# MRCS-Nano-Ard-Relay-Breakout.net
KiCad netlist of a schematic drawn in EAGLE
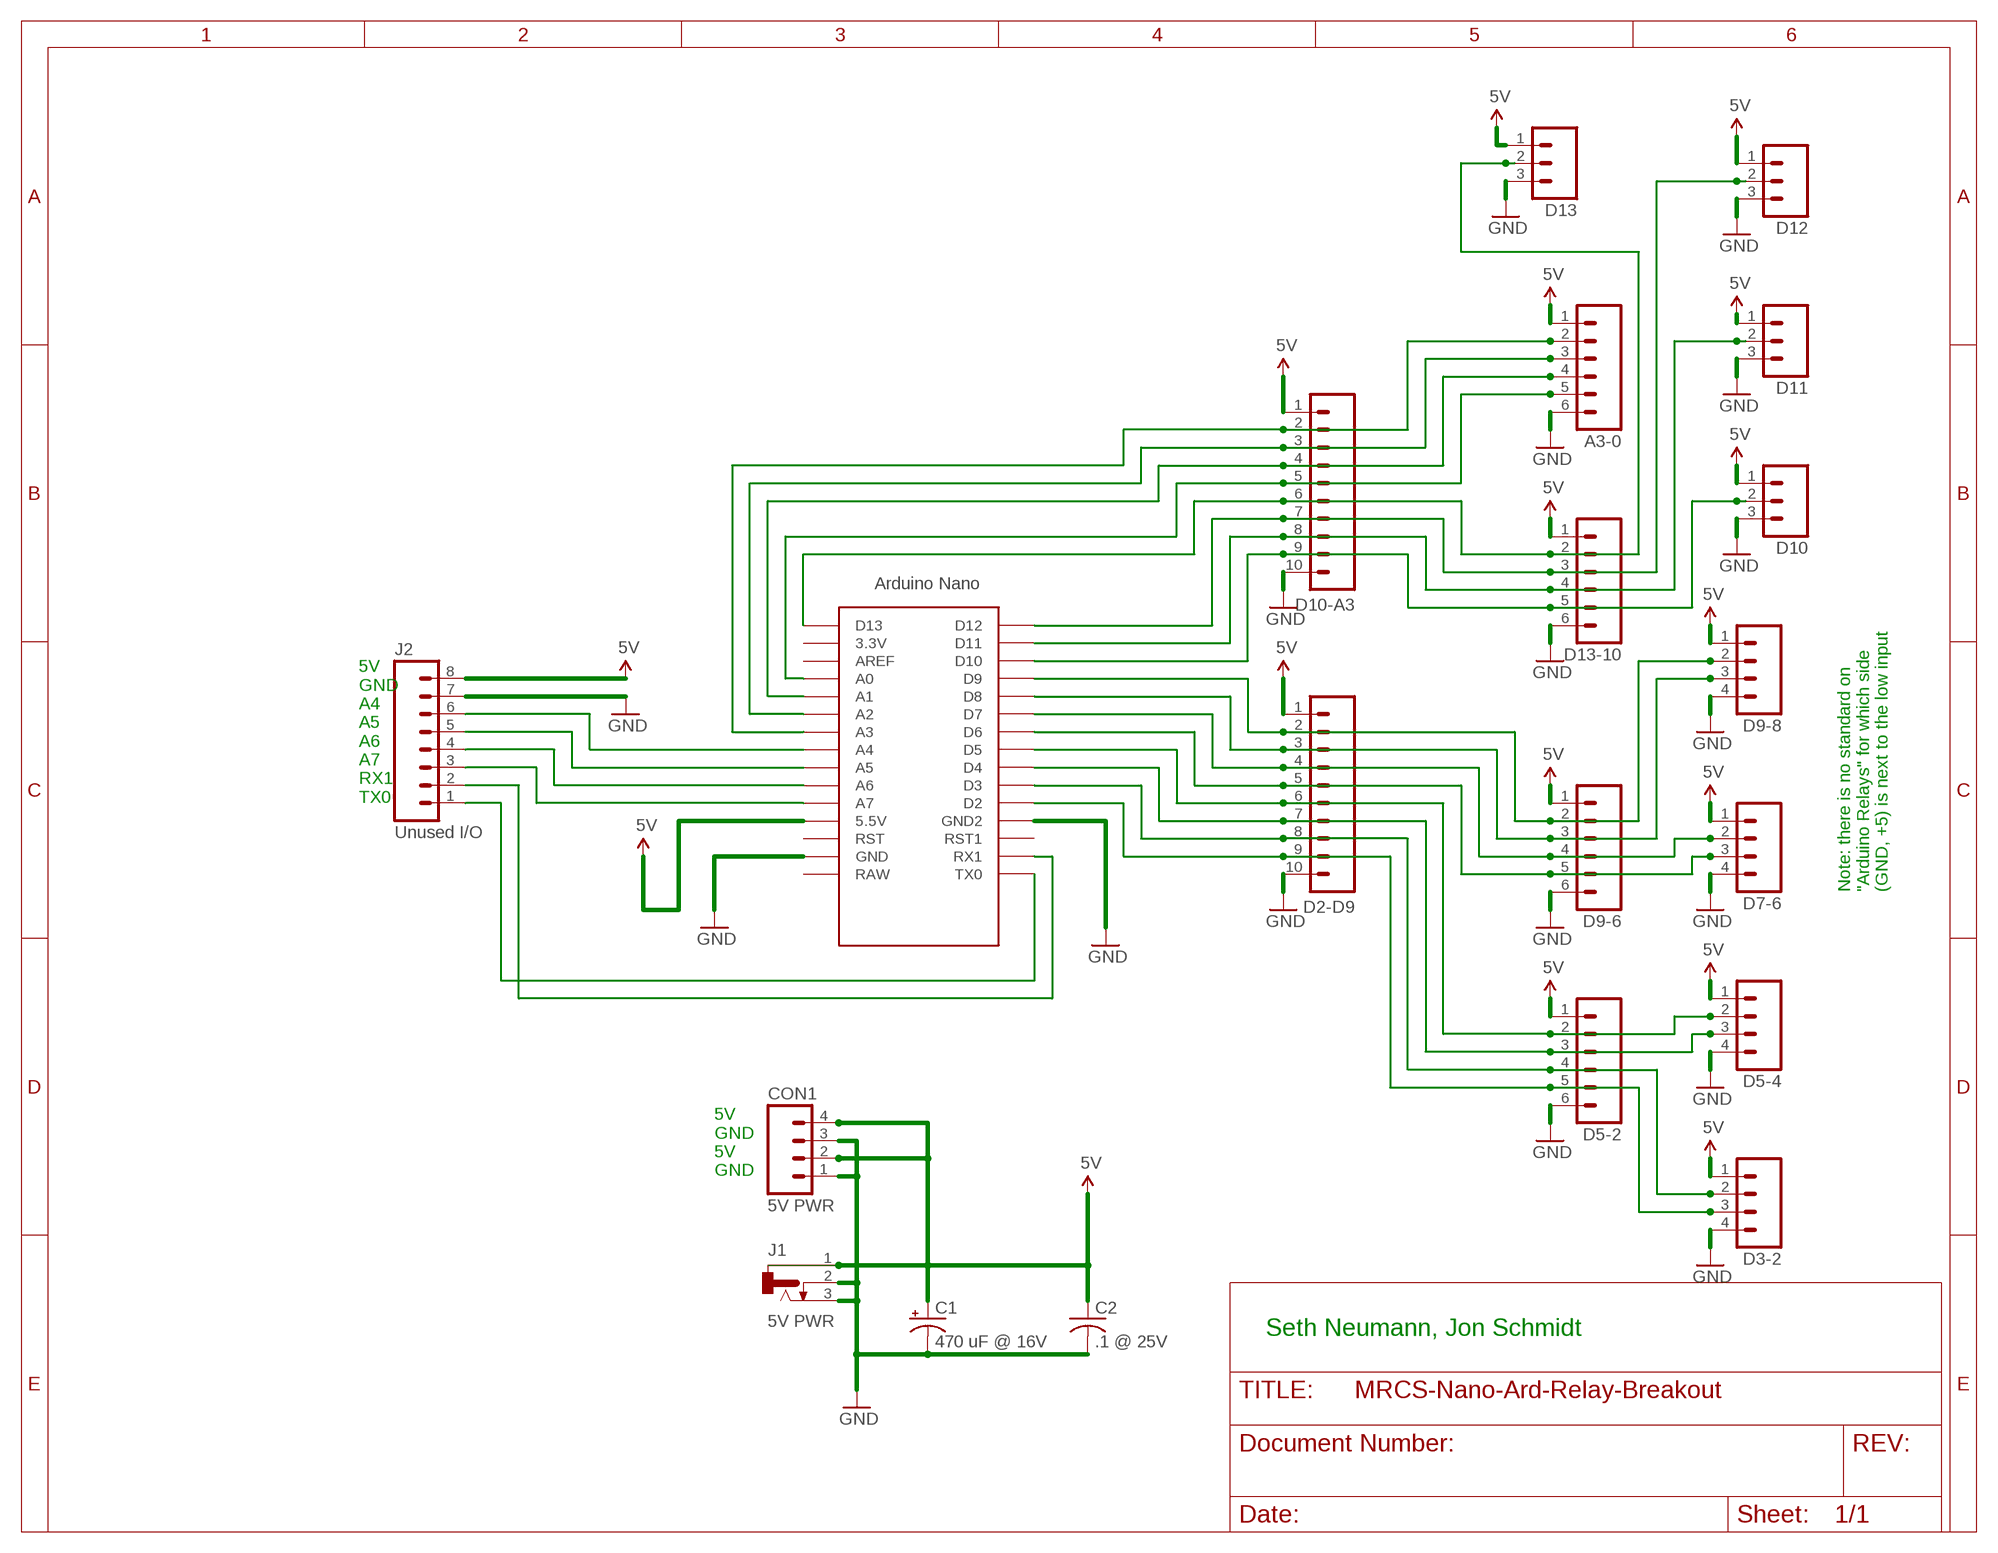
[diagram p0: schematic, sheet 1]

(export (version "E")
  (design (tool "Eeschema 10.0.6"))
  (components
    (comp (ref "A3-0")
      (value "CONNECTOR-M06LOCK")
      (footprint "eagle-import:1X06_LOCK")
      (libsource (lib "eagle-import") (part "CONNECTOR-M06LOCK"))
    )
    (comp (ref "C1")
      (value "470 uF @ 16V")
      (footprint "eagle-import:E3.5-10")
      (libsource (lib "eagle-import") (part "CAP-POLPTH-3.5MM"))
    )
    (comp (ref "C2")
      (value ".1 @ 25V")
      (footprint "eagle-import:C-PTH-0.100")
      (libsource (lib "eagle-import") (part "CAPPTH2"))
    )
    (comp (ref "CON1")
      (value "5V PWR")
      (footprint "eagle-import:SCREWTERMINAL-3.5MM-4_LOCK")
      (libsource (lib "eagle-import") (part "CONNECTOR-M04SCREW_LOCK"))
    )
    (comp (ref "D2-D9")
      (value "CONNECTOR-M102MM")
      (footprint "eagle-import:1X10-2MM")
      (libsource (lib "eagle-import") (part "CONNECTOR-M102MM"))
    )
    (comp (ref "D3-2")
      (value "CONNECTOR-M04LOCK")
      (footprint "eagle-import:1X04_LOCK")
      (libsource (lib "eagle-import") (part "CONNECTOR-M04LOCK"))
    )
    (comp (ref "D5-2")
      (value "CONNECTOR-M06LOCK")
      (footprint "eagle-import:1X06_LOCK")
      (libsource (lib "eagle-import") (part "CONNECTOR-M06LOCK"))
    )
    (comp (ref "D5-4")
      (value "CONNECTOR-M04LOCK")
      (footprint "eagle-import:1X04_LOCK")
      (libsource (lib "eagle-import") (part "CONNECTOR-M04LOCK"))
    )
    (comp (ref "D7-6")
      (value "CONNECTOR-M04LOCK")
      (footprint "eagle-import:1X04_LOCK")
      (libsource (lib "eagle-import") (part "CONNECTOR-M04LOCK"))
    )
    (comp (ref "D9-6")
      (value "CONNECTOR-M06LOCK")
      (footprint "eagle-import:1X06_LOCK")
      (libsource (lib "eagle-import") (part "CONNECTOR-M06LOCK"))
    )
    (comp (ref "D9-8")
      (value "CONNECTOR-M04LOCK")
      (footprint "eagle-import:1X04_LOCK")
      (libsource (lib "eagle-import") (part "CONNECTOR-M04LOCK"))
    )
    (comp (ref "D10")
      (value "CONNECTOR-M03MOLEX-254-LOCK")
      (footprint "eagle-import:MOLEX-1X3_LOCK")
      (libsource (lib "eagle-import") (part "CONNECTOR-M03MOLEX-254-LOCK"))
    )
    (comp (ref "D10-A3")
      (value "CONNECTOR-M102MM")
      (footprint "eagle-import:1X10-2MM")
      (libsource (lib "eagle-import") (part "CONNECTOR-M102MM"))
    )
    (comp (ref "D11")
      (value "CONNECTOR-M03MOLEX-254-LOCK")
      (footprint "eagle-import:MOLEX-1X3_LOCK")
      (libsource (lib "eagle-import") (part "CONNECTOR-M03MOLEX-254-LOCK"))
    )
    (comp (ref "D12")
      (value "CONNECTOR-M03MOLEX-254-LOCK")
      (footprint "eagle-import:MOLEX-1X3_LOCK")
      (libsource (lib "eagle-import") (part "CONNECTOR-M03MOLEX-254-LOCK"))
    )
    (comp (ref "D13")
      (value "CONNECTOR-M03MOLEX-254-LOCK")
      (footprint "eagle-import:MOLEX-1X3_LOCK")
      (libsource (lib "eagle-import") (part "CONNECTOR-M03MOLEX-254-LOCK"))
    )
    (comp (ref "D13-10")
      (value "CONNECTOR-M06LOCK")
      (footprint "eagle-import:1X06_LOCK")
      (libsource (lib "eagle-import") (part "CONNECTOR-M06LOCK"))
    )
    (comp (ref "J1")
      (value "5V PWR")
      (footprint "eagle-import:DCJ0202")
      (libsource (lib "eagle-import") (part "CONNECTOR-DC-POWER-RA"))
    )
    (comp (ref "J2")
      (value "Unused I/O")
      (footprint "eagle-import:1X08_LOCK")
      (libsource (lib "eagle-import") (part "CONNECTOR-M08LOCK"))
    )
    (comp (ref "U$1")
      (value "NANO")
      (footprint "eagle-import:NANO")
      (libsource (lib "eagle-import") (part "NANO"))
    )
  )
  (nets
    (net (code "1") (name "5V") (class "Default")
      (node (ref "A3-0") (pin "1") (pinfunction "1_1") (pintype "passive"))
      (node (ref "C1") (pin "+") (pinfunction "+_+") (pintype "passive"))
      (node (ref "C2") (pin "1") (pinfunction "1_1") (pintype "passive"))
      (node (ref "CON1") (pin "2") (pinfunction "2_2") (pintype "passive"))
      (node (ref "CON1") (pin "4") (pinfunction "4_4") (pintype "passive"))
      (node (ref "D10") (pin "1") (pinfunction "1_1") (pintype "passive"))
      (node (ref "D10-A3") (pin "1") (pinfunction "1_1") (pintype "passive"))
      (node (ref "D11") (pin "1") (pinfunction "1_1") (pintype "passive"))
      (node (ref "D12") (pin "1") (pinfunction "1_1") (pintype "passive"))
      (node (ref "D13") (pin "1") (pinfunction "1_1") (pintype "passive"))
      (node (ref "D13-10") (pin "1") (pinfunction "1_1") (pintype "passive"))
      (node (ref "D2-D9") (pin "1") (pinfunction "1_1") (pintype "passive"))
      (node (ref "D3-2") (pin "1") (pinfunction "1_1") (pintype "passive"))
      (node (ref "D5-2") (pin "1") (pinfunction "1_1") (pintype "passive"))
      (node (ref "D5-4") (pin "1") (pinfunction "1_1") (pintype "passive"))
      (node (ref "D7-6") (pin "1") (pinfunction "1_1") (pintype "passive"))
      (node (ref "D9-6") (pin "1") (pinfunction "1_1") (pintype "passive"))
      (node (ref "D9-8") (pin "1") (pinfunction "1_1") (pintype "passive"))
      (node (ref "J1") (pin "1") (pinfunction "1_1") (pintype "passive"))
      (node (ref "J2") (pin "8") (pinfunction "8_8") (pintype "passive"))
      (node (ref "U$1") (pin "5V") (pinfunction "5.5V_5V") (pintype "bidirectional"))
    )
    (net (code "2") (name "GND") (class "Default")
      (node (ref "A3-0") (pin "6") (pinfunction "6_6") (pintype "passive"))
      (node (ref "C1") (pin "-") (pinfunction "-_-") (pintype "passive"))
      (node (ref "C2") (pin "2") (pinfunction "2_2") (pintype "passive"))
      (node (ref "CON1") (pin "1") (pinfunction "1_1") (pintype "passive"))
      (node (ref "CON1") (pin "3") (pinfunction "3_3") (pintype "passive"))
      (node (ref "D10") (pin "3") (pinfunction "3_3") (pintype "passive"))
      (node (ref "D10-A3") (pin "10") (pinfunction "10_10") (pintype "passive"))
      (node (ref "D11") (pin "3") (pinfunction "3_3") (pintype "passive"))
      (node (ref "D12") (pin "3") (pinfunction "3_3") (pintype "passive"))
      (node (ref "D13") (pin "3") (pinfunction "3_3") (pintype "passive"))
      (node (ref "D13-10") (pin "6") (pinfunction "6_6") (pintype "passive"))
      (node (ref "D2-D9") (pin "10") (pinfunction "10_10") (pintype "passive"))
      (node (ref "D3-2") (pin "4") (pinfunction "4_4") (pintype "passive"))
      (node (ref "D5-2") (pin "6") (pinfunction "6_6") (pintype "passive"))
      (node (ref "D5-4") (pin "4") (pinfunction "4_4") (pintype "passive"))
      (node (ref "D7-6") (pin "4") (pinfunction "4_4") (pintype "passive"))
      (node (ref "D9-6") (pin "6") (pinfunction "6_6") (pintype "passive"))
      (node (ref "D9-8") (pin "4") (pinfunction "4_4") (pintype "passive"))
      (node (ref "J1") (pin "2") (pinfunction "2_2") (pintype "passive"))
      (node (ref "J1") (pin "3") (pinfunction "3_3") (pintype "passive"))
      (node (ref "J2") (pin "7") (pinfunction "7_7") (pintype "passive"))
      (node (ref "U$1") (pin "GND") (pinfunction "GND_GND") (pintype "bidirectional"))
      (node (ref "U$1") (pin "GND1") (pinfunction "GND2_GND1") (pintype "bidirectional"))
    )
    (net (code "3") (name "Net-(A3-0-Pad2)") (class "Default")
      (node (ref "A3-0") (pin "2") (pinfunction "2_2") (pintype "passive"))
      (node (ref "D10-A3") (pin "2") (pinfunction "2_2") (pintype "passive"))
      (node (ref "U$1") (pin "A3") (pinfunction "A3_A3") (pintype "bidirectional"))
    )
    (net (code "4") (name "Net-(A3-0-Pad3)") (class "Default")
      (node (ref "A3-0") (pin "3") (pinfunction "3_3") (pintype "passive"))
      (node (ref "D10-A3") (pin "3") (pinfunction "3_3") (pintype "passive"))
      (node (ref "U$1") (pin "A2") (pinfunction "A2_A2") (pintype "bidirectional"))
    )
    (net (code "5") (name "Net-(A3-0-Pad4)") (class "Default")
      (node (ref "A3-0") (pin "4") (pinfunction "4_4") (pintype "passive"))
      (node (ref "D10-A3") (pin "4") (pinfunction "4_4") (pintype "passive"))
      (node (ref "U$1") (pin "A1") (pinfunction "A1_A1") (pintype "bidirectional"))
    )
    (net (code "6") (name "Net-(A3-0-Pad5)") (class "Default")
      (node (ref "A3-0") (pin "5") (pinfunction "5_5") (pintype "passive"))
      (node (ref "D10-A3") (pin "5") (pinfunction "5_5") (pintype "passive"))
      (node (ref "U$1") (pin "A0") (pinfunction "A0_A0") (pintype "bidirectional"))
    )
    (net (code "7") (name "Net-(D2-D9-Pad2)") (class "Default")
      (node (ref "D2-D9") (pin "2") (pinfunction "2_2") (pintype "passive"))
      (node (ref "D9-6") (pin "2") (pinfunction "2_2") (pintype "passive"))
      (node (ref "D9-8") (pin "2") (pinfunction "2_2") (pintype "passive"))
      (node (ref "U$1") (pin "D9") (pinfunction "D9_D9") (pintype "bidirectional"))
    )
    (net (code "8") (name "Net-(D2-D9-Pad3)") (class "Default")
      (node (ref "D2-D9") (pin "3") (pinfunction "3_3") (pintype "passive"))
      (node (ref "D9-6") (pin "3") (pinfunction "3_3") (pintype "passive"))
      (node (ref "D9-8") (pin "3") (pinfunction "3_3") (pintype "passive"))
      (node (ref "U$1") (pin "D8") (pinfunction "D8_D8") (pintype "bidirectional"))
    )
    (net (code "9") (name "Net-(D2-D9-Pad4)") (class "Default")
      (node (ref "D2-D9") (pin "4") (pinfunction "4_4") (pintype "passive"))
      (node (ref "D7-6") (pin "2") (pinfunction "2_2") (pintype "passive"))
      (node (ref "D9-6") (pin "4") (pinfunction "4_4") (pintype "passive"))
      (node (ref "U$1") (pin "D7") (pinfunction "D7_D7") (pintype "bidirectional"))
    )
    (net (code "10") (name "Net-(D2-D9-Pad5)") (class "Default")
      (node (ref "D2-D9") (pin "5") (pinfunction "5_5") (pintype "passive"))
      (node (ref "D7-6") (pin "3") (pinfunction "3_3") (pintype "passive"))
      (node (ref "D9-6") (pin "5") (pinfunction "5_5") (pintype "passive"))
      (node (ref "U$1") (pin "D6") (pinfunction "D6_D6") (pintype "bidirectional"))
    )
    (net (code "11") (name "Net-(D2-D9-Pad6)") (class "Default")
      (node (ref "D2-D9") (pin "6") (pinfunction "6_6") (pintype "passive"))
      (node (ref "D5-2") (pin "2") (pinfunction "2_2") (pintype "passive"))
      (node (ref "D5-4") (pin "2") (pinfunction "2_2") (pintype "passive"))
      (node (ref "U$1") (pin "D5") (pinfunction "D5_D5") (pintype "bidirectional"))
    )
    (net (code "12") (name "Net-(D2-D9-Pad7)") (class "Default")
      (node (ref "D2-D9") (pin "7") (pinfunction "7_7") (pintype "passive"))
      (node (ref "D5-2") (pin "3") (pinfunction "3_3") (pintype "passive"))
      (node (ref "D5-4") (pin "3") (pinfunction "3_3") (pintype "passive"))
      (node (ref "U$1") (pin "D4") (pinfunction "D4_D4") (pintype "bidirectional"))
    )
    (net (code "13") (name "Net-(D2-D9-Pad8)") (class "Default")
      (node (ref "D2-D9") (pin "8") (pinfunction "8_8") (pintype "passive"))
      (node (ref "D3-2") (pin "2") (pinfunction "2_2") (pintype "passive"))
      (node (ref "D5-2") (pin "4") (pinfunction "4_4") (pintype "passive"))
      (node (ref "U$1") (pin "D3") (pinfunction "D3_D3") (pintype "bidirectional"))
    )
    (net (code "14") (name "Net-(D2-D9-Pad9)") (class "Default")
      (node (ref "D2-D9") (pin "9") (pinfunction "9_9") (pintype "passive"))
      (node (ref "D3-2") (pin "3") (pinfunction "3_3") (pintype "passive"))
      (node (ref "D5-2") (pin "5") (pinfunction "5_5") (pintype "passive"))
      (node (ref "U$1") (pin "D2") (pinfunction "D2_D2") (pintype "bidirectional"))
    )
    (net (code "15") (name "Net-(D10-A3-Pad6)") (class "Default")
      (node (ref "D10-A3") (pin "6") (pinfunction "6_6") (pintype "passive"))
      (node (ref "D13") (pin "2") (pinfunction "2_2") (pintype "passive"))
      (node (ref "D13-10") (pin "2") (pinfunction "2_2") (pintype "passive"))
      (node (ref "U$1") (pin "D13") (pinfunction "D13_D13") (pintype "bidirectional"))
    )
    (net (code "16") (name "Net-(D10-A3-Pad7)") (class "Default")
      (node (ref "D10-A3") (pin "7") (pinfunction "7_7") (pintype "passive"))
      (node (ref "D12") (pin "2") (pinfunction "2_2") (pintype "passive"))
      (node (ref "D13-10") (pin "3") (pinfunction "3_3") (pintype "passive"))
      (node (ref "U$1") (pin "D12") (pinfunction "D12_D12") (pintype "bidirectional"))
    )
    (net (code "17") (name "Net-(D10-A3-Pad8)") (class "Default")
      (node (ref "D10-A3") (pin "8") (pinfunction "8_8") (pintype "passive"))
      (node (ref "D11") (pin "2") (pinfunction "2_2") (pintype "passive"))
      (node (ref "D13-10") (pin "4") (pinfunction "4_4") (pintype "passive"))
      (node (ref "U$1") (pin "D11") (pinfunction "D11_D11") (pintype "bidirectional"))
    )
    (net (code "18") (name "Net-(D10-A3-Pad9)") (class "Default")
      (node (ref "D10") (pin "2") (pinfunction "2_2") (pintype "passive"))
      (node (ref "D10-A3") (pin "9") (pinfunction "9_9") (pintype "passive"))
      (node (ref "D13-10") (pin "5") (pinfunction "5_5") (pintype "passive"))
      (node (ref "U$1") (pin "D10") (pinfunction "D10_D10") (pintype "bidirectional"))
    )
    (net (code "19") (name "Net-(J2-Pad1)") (class "Default")
      (node (ref "J2") (pin "1") (pinfunction "1_1") (pintype "passive"))
      (node (ref "U$1") (pin "TX0") (pinfunction "TX0_TX0") (pintype "bidirectional"))
    )
    (net (code "20") (name "Net-(J2-Pad2)") (class "Default")
      (node (ref "J2") (pin "2") (pinfunction "2_2") (pintype "passive"))
      (node (ref "U$1") (pin "RX1") (pinfunction "RX1_RX1") (pintype "bidirectional"))
    )
    (net (code "21") (name "Net-(J2-Pad3)") (class "Default")
      (node (ref "J2") (pin "3") (pinfunction "3_3") (pintype "passive"))
      (node (ref "U$1") (pin "A7") (pinfunction "A7_A7") (pintype "bidirectional"))
    )
    (net (code "22") (name "Net-(J2-Pad4)") (class "Default")
      (node (ref "J2") (pin "4") (pinfunction "4_4") (pintype "passive"))
      (node (ref "U$1") (pin "A6") (pinfunction "A6_A6") (pintype "bidirectional"))
    )
    (net (code "23") (name "Net-(J2-Pad5)") (class "Default")
      (node (ref "J2") (pin "5") (pinfunction "5_5") (pintype "passive"))
      (node (ref "U$1") (pin "A5") (pinfunction "A5_A5") (pintype "bidirectional"))
    )
    (net (code "24") (name "Net-(J2-Pad6)") (class "Default")
      (node (ref "J2") (pin "6") (pinfunction "6_6") (pintype "passive"))
      (node (ref "U$1") (pin "A4") (pinfunction "A4_A4") (pintype "bidirectional"))
    )
    (net (code "25") (name "unconnected-(U$1-Pad3.3V)") (class "Default")
      (node (ref "U$1") (pin "3.3V") (pinfunction "3.3V_3.3V") (pintype "bidirectional"))
    )
    (net (code "26") (name "unconnected-(U$1-PadAREF)") (class "Default")
      (node (ref "U$1") (pin "AREF") (pinfunction "AREF_AREF") (pintype "bidirectional"))
    )
    (net (code "27") (name "unconnected-(U$1-PadRAW)") (class "Default")
      (node (ref "U$1") (pin "RAW") (pinfunction "RAW_RAW") (pintype "bidirectional"))
    )
    (net (code "28") (name "unconnected-(U$1-PadRST)") (class "Default")
      (node (ref "U$1") (pin "RST") (pinfunction "RST_RST") (pintype "bidirectional"))
    )
    (net (code "29") (name "unconnected-(U$1-PadRST1)") (class "Default")
      (node (ref "U$1") (pin "RST1") (pinfunction "RST1_RST1") (pintype "bidirectional"))
    )
  )
)
